# PIC32.net
KiCad netlist of a schematic drawn in EAGLE
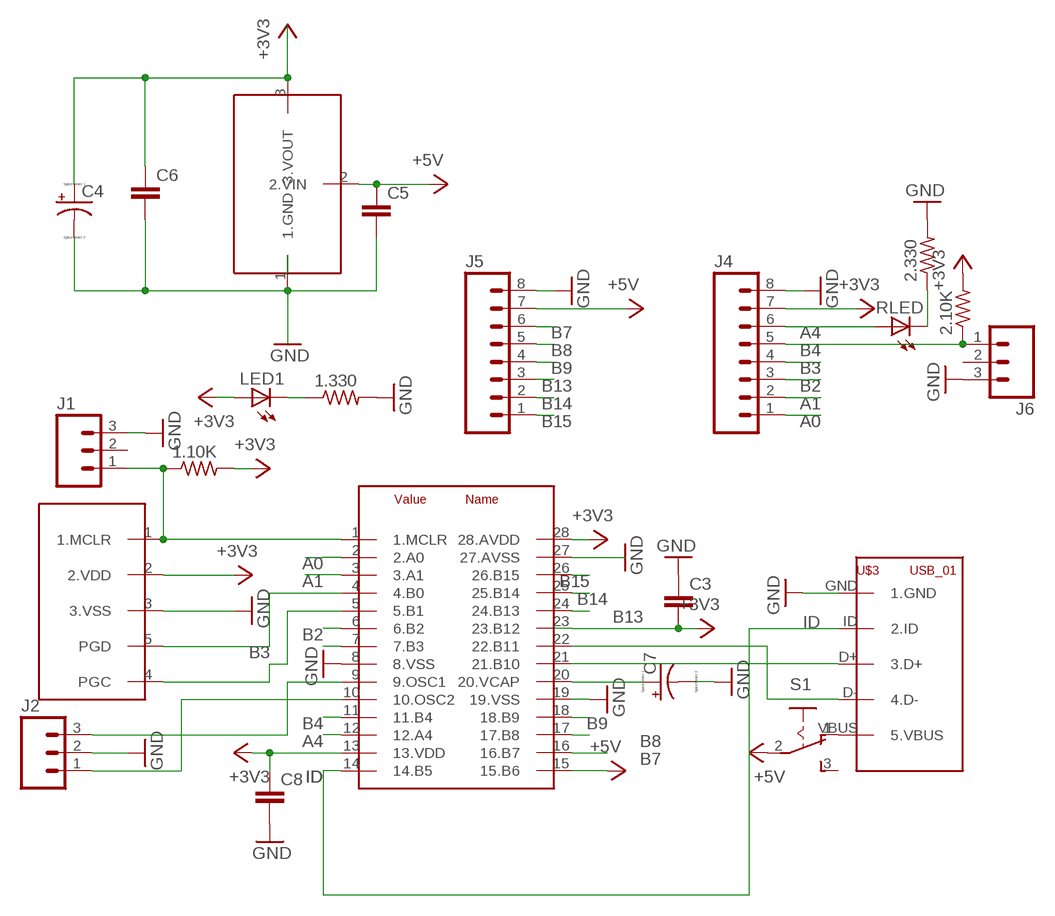
[diagram p0: schematic, sheet 1]

(export (version "E")
  (design (tool "Eeschema 10.0.6"))
  (components
    (comp (ref "1.10K")
      (value "R-US_0207/10")
      (footprint "eagle-import:0207_10")
      (libsource (lib "eagle-import") (part "R-US_0207/10"))
    )
    (comp (ref "1.330")
      (value "R-US_0207/10")
      (footprint "eagle-import:0207_10")
      (libsource (lib "eagle-import") (part "R-US_0207/10"))
    )
    (comp (ref "2.10K")
      (value "R-US_0207/10")
      (footprint "eagle-import:0207_10")
      (libsource (lib "eagle-import") (part "R-US_0207/10"))
    )
    (comp (ref "2.330")
      (value "R-US_0207/10")
      (footprint "eagle-import:0207_10")
      (libsource (lib "eagle-import") (part "R-US_0207/10"))
    )
    (comp (ref "C3")
      (value "C5/3")
      (footprint "eagle-import:C5B3")
      (libsource (lib "eagle-import") (part "C5/3"))
    )
    (comp (ref "C4")
      (value "CPOL-USB45181B")
      (footprint "eagle-import:B45181B")
      (libsource (lib "eagle-import") (part "CPOL-USB45181B"))
    )
    (comp (ref "C5")
      (value "C5/3")
      (footprint "eagle-import:C5B3")
      (libsource (lib "eagle-import") (part "C5/3"))
    )
    (comp (ref "C6")
      (value "C5/3")
      (footprint "eagle-import:C5B3")
      (libsource (lib "eagle-import") (part "C5/3"))
    )
    (comp (ref "C7")
      (value "CPOL-USB45181B")
      (footprint "eagle-import:B45181B")
      (libsource (lib "eagle-import") (part "CPOL-USB45181B"))
    )
    (comp (ref "C8")
      (value "C5/3")
      (footprint "eagle-import:C5B3")
      (libsource (lib "eagle-import") (part "C5/3"))
    )
    (comp (ref "J1")
      (value "M03PTH")
      (footprint "eagle-import:1X03")
      (libsource (lib "eagle-import") (part "M03PTH"))
    )
    (comp (ref "J2")
      (value "M03PTH")
      (footprint "eagle-import:1X03")
      (libsource (lib "eagle-import") (part "M03PTH"))
    )
    (comp (ref "J4")
      (value "M08")
      (footprint "eagle-import:1X08_ROUND")
      (libsource (lib "eagle-import") (part "M08"))
    )
    (comp (ref "J5")
      (value "M08")
      (footprint "eagle-import:1X08_ROUND")
      (libsource (lib "eagle-import") (part "M08"))
    )
    (comp (ref "J6")
      (value "M03PTH")
      (footprint "eagle-import:1X03")
      (libsource (lib "eagle-import") (part "M03PTH"))
    )
    (comp (ref "LED1")
      (value "LED3MM")
      (footprint "eagle-import:LED3MM")
      (libsource (lib "eagle-import") (part "LED3MM"))
    )
    (comp (ref "RLED")
      (value "LED3MM")
      (footprint "eagle-import:LED3MM")
      (libsource (lib "eagle-import") (part "LED3MM"))
    )
    (comp (ref "S1")
      (value "255SB")
      (footprint "eagle-import:255SB")
      (libsource (lib "eagle-import") (part "255SB"))
    )
    (comp (ref "U$1")
      (value "PIC28")
      (footprint "eagle-import:DIL28-3")
      (libsource (lib "eagle-import") (part "PIC28"))
    )
    (comp (ref "U$2")
      (value "MCP1702")
      (footprint "eagle-import:TO92")
      (libsource (lib "eagle-import") (part "MCP1702"))
    )
    (comp (ref "U$3")
      (value "USB_01")
      (footprint "eagle-import:USB-MB-H")
      (libsource (lib "eagle-import") (part "USB_01"))
    )
    (comp (ref "U$5")
      (value "SWITCH_M05")
      (footprint "eagle-import:1X05")
      (libsource (lib "eagle-import") (part "SWITCH_M05"))
    )
  )
  (nets
    (net (code "1") (name "+3V3") (class "Default")
      (node (ref "1.10K") (pin "2") (pinfunction "2_2") (pintype "passive"))
      (node (ref "2.10K") (pin "2") (pinfunction "2_2") (pintype "passive"))
      (node (ref "C3") (pin "2") (pinfunction "2_2") (pintype "passive"))
      (node (ref "C8") (pin "1") (pinfunction "1_1") (pintype "passive"))
      (node (ref "J4") (pin "7") (pinfunction "7_7") (pintype "passive"))
      (node (ref "LED1") (pin "A") (pinfunction "A_A") (pintype "passive"))
      (node (ref "U$1") (pin "13") (pinfunction "13.VDD_13") (pintype "bidirectional"))
      (node (ref "U$1") (pin "23") (pinfunction "23.B12_23") (pintype "bidirectional"))
      (node (ref "U$1") (pin "28") (pinfunction "28.AVDD_28") (pintype "bidirectional"))
      (node (ref "U$5") (pin "2") (pinfunction "2.VDD_2") (pintype "bidirectional"))
    )
    (net (code "2") (name "+5V") (class "Default")
      (node (ref "C5") (pin "1") (pinfunction "1_1") (pintype "passive"))
      (node (ref "J5") (pin "7") (pinfunction "7_7") (pintype "passive"))
      (node (ref "S1") (pin "2") (pinfunction "P_2") (pintype "passive"))
      (node (ref "U$1") (pin "15") (pinfunction "15.B6_15") (pintype "bidirectional"))
      (node (ref "U$2") (pin "2") (pinfunction "2.VIN_2") (pintype "bidirectional"))
    )
    (net (code "3") (name "/A0") (class "Default")
      (node (ref "J4") (pin "1") (pinfunction "1_1") (pintype "passive"))
      (node (ref "U$1") (pin "2") (pinfunction "2.A0_2") (pintype "bidirectional"))
    )
    (net (code "4") (name "/A1") (class "Default")
      (node (ref "J4") (pin "2") (pinfunction "2_2") (pintype "passive"))
      (node (ref "U$1") (pin "3") (pinfunction "3.A1_3") (pintype "bidirectional"))
    )
    (net (code "5") (name "/A4") (class "Default")
      (node (ref "J4") (pin "6") (pinfunction "6_6") (pintype "passive"))
      (node (ref "RLED") (pin "A") (pinfunction "A_A") (pintype "passive"))
      (node (ref "U$1") (pin "12") (pinfunction "12.A4_12") (pintype "bidirectional"))
    )
    (net (code "6") (name "/B2") (class "Default")
      (node (ref "J4") (pin "3") (pinfunction "3_3") (pintype "passive"))
      (node (ref "U$1") (pin "6") (pinfunction "6.B2_6") (pintype "bidirectional"))
    )
    (net (code "7") (name "/B3") (class "Default")
      (node (ref "J4") (pin "4") (pinfunction "4_4") (pintype "passive"))
      (node (ref "U$1") (pin "7") (pinfunction "7.B3_7") (pintype "bidirectional"))
    )
    (net (code "8") (name "/B4") (class "Default")
      (node (ref "2.10K") (pin "1") (pinfunction "1_1") (pintype "passive"))
      (node (ref "J4") (pin "5") (pinfunction "5_5") (pintype "passive"))
      (node (ref "J6") (pin "1") (pinfunction "1_1") (pintype "passive"))
      (node (ref "U$1") (pin "11") (pinfunction "11.B4_11") (pintype "bidirectional"))
    )
    (net (code "9") (name "/B7") (class "Default")
      (node (ref "J5") (pin "6") (pinfunction "6_6") (pintype "passive"))
      (node (ref "U$1") (pin "16") (pinfunction "16.B7_16") (pintype "bidirectional"))
    )
    (net (code "10") (name "/B8") (class "Default")
      (node (ref "J5") (pin "5") (pinfunction "5_5") (pintype "passive"))
      (node (ref "U$1") (pin "17") (pinfunction "17.B8_17") (pintype "bidirectional"))
    )
    (net (code "11") (name "/B9") (class "Default")
      (node (ref "J5") (pin "4") (pinfunction "4_4") (pintype "passive"))
      (node (ref "U$1") (pin "18") (pinfunction "18.B9_18") (pintype "bidirectional"))
    )
    (net (code "12") (name "/B13") (class "Default")
      (node (ref "J5") (pin "3") (pinfunction "3_3") (pintype "passive"))
      (node (ref "U$1") (pin "24") (pinfunction "24.B13_24") (pintype "bidirectional"))
    )
    (net (code "13") (name "/B14") (class "Default")
      (node (ref "J5") (pin "2") (pinfunction "2_2") (pintype "passive"))
      (node (ref "U$1") (pin "25") (pinfunction "25.B14_25") (pintype "bidirectional"))
    )
    (net (code "14") (name "/B15") (class "Default")
      (node (ref "J5") (pin "1") (pinfunction "1_1") (pintype "passive"))
      (node (ref "U$1") (pin "26") (pinfunction "26.B15_26") (pintype "bidirectional"))
    )
    (net (code "15") (name "/ID") (class "Default")
      (node (ref "U$1") (pin "14") (pinfunction "14.B5_14") (pintype "bidirectional"))
      (node (ref "U$3") (pin "ID") (pinfunction "2.ID_ID") (pintype "bidirectional"))
    )
    (net (code "16") (name "GND") (class "Default")
      (node (ref "1.330") (pin "2") (pinfunction "2_2") (pintype "passive"))
      (node (ref "2.330") (pin "2") (pinfunction "2_2") (pintype "passive"))
      (node (ref "C3") (pin "1") (pinfunction "1_1") (pintype "passive"))
      (node (ref "C7") (pin "-") (pinfunction "-_-") (pintype "passive"))
      (node (ref "C8") (pin "2") (pinfunction "2_2") (pintype "passive"))
      (node (ref "J1") (pin "3") (pinfunction "3_3") (pintype "passive"))
      (node (ref "J2") (pin "2") (pinfunction "2_2") (pintype "passive"))
      (node (ref "J4") (pin "8") (pinfunction "8_8") (pintype "passive"))
      (node (ref "J5") (pin "8") (pinfunction "8_8") (pintype "passive"))
      (node (ref "J6") (pin "3") (pinfunction "3_3") (pintype "passive"))
      (node (ref "U$1") (pin "19") (pinfunction "19.VSS_19") (pintype "bidirectional"))
      (node (ref "U$1") (pin "8") (pinfunction "8.VSS_8") (pintype "bidirectional"))
      (node (ref "U$3") (pin "GND") (pinfunction "1.GND_GND") (pintype "bidirectional"))
      (node (ref "U$5") (pin "3") (pinfunction "3.VSS_3") (pintype "bidirectional"))
    )
    (net (code "17") (name "Net-(LED1-C)") (class "Default")
      (node (ref "1.330") (pin "1") (pinfunction "1_1") (pintype "passive"))
      (node (ref "LED1") (pin "K") (pinfunction "C_K") (pintype "passive"))
    )
    (net (code "18") (name "Net-(RLED-C)") (class "Default")
      (node (ref "2.330") (pin "1") (pinfunction "1_1") (pintype "passive"))
      (node (ref "RLED") (pin "K") (pinfunction "C_K") (pintype "passive"))
    )
    (net (code "19") (name "Net-(S1-O)") (class "Default")
      (node (ref "S1") (pin "1") (pinfunction "O_1") (pintype "passive"))
      (node (ref "U$3") (pin "VBUS") (pinfunction "5.VBUS_VBUS") (pintype "bidirectional"))
    )
    (net (code "20") (name "Net-(U$1-1.MCLR)") (class "Default")
      (node (ref "1.10K") (pin "1") (pinfunction "1_1") (pintype "passive"))
      (node (ref "J1") (pin "1") (pinfunction "1_1") (pintype "passive"))
      (node (ref "U$1") (pin "1") (pinfunction "1.MCLR_1") (pintype "bidirectional"))
      (node (ref "U$5") (pin "1") (pinfunction "1.MCLR_1") (pintype "bidirectional"))
    )
    (net (code "21") (name "Net-(U$1-4.B0)") (class "Default")
      (node (ref "U$1") (pin "4") (pinfunction "4.B0_4") (pintype "bidirectional"))
      (node (ref "U$5") (pin "5") (pinfunction "PGD_5") (pintype "bidirectional"))
    )
    (net (code "22") (name "Net-(U$1-5.B1)") (class "Default")
      (node (ref "U$1") (pin "5") (pinfunction "5.B1_5") (pintype "bidirectional"))
      (node (ref "U$5") (pin "4") (pinfunction "PGC_4") (pintype "bidirectional"))
    )
    (net (code "23") (name "Net-(U$1-9.OSC1)") (class "Default")
      (node (ref "J2") (pin "3") (pinfunction "3_3") (pintype "passive"))
      (node (ref "U$1") (pin "9") (pinfunction "9.OSC1_9") (pintype "bidirectional"))
    )
    (net (code "24") (name "Net-(U$1-10.OSC2)") (class "Default")
      (node (ref "J2") (pin "1") (pinfunction "1_1") (pintype "passive"))
      (node (ref "U$1") (pin "10") (pinfunction "10.OSC2_10") (pintype "bidirectional"))
    )
    (net (code "25") (name "Net-(U$1-20.VCAP)") (class "Default")
      (node (ref "C7") (pin "+") (pinfunction "+_+") (pintype "passive"))
      (node (ref "U$1") (pin "20") (pinfunction "20.VCAP_20") (pintype "bidirectional"))
    )
    (net (code "26") (name "Net-(U$1-21.B10)") (class "Default")
      (node (ref "U$1") (pin "21") (pinfunction "21.B10_21") (pintype "bidirectional"))
      (node (ref "U$3") (pin "D+") (pinfunction "3.D+_D+") (pintype "bidirectional"))
    )
    (net (code "27") (name "Net-(U$1-22.B11)") (class "Default")
      (node (ref "U$1") (pin "22") (pinfunction "22.B11_22") (pintype "bidirectional"))
      (node (ref "U$3") (pin "D-") (pinfunction "4.D-_D-") (pintype "bidirectional"))
    )
    (net (code "28") (name "Net-(U$2-1.GND)") (class "Default")
      (node (ref "C4") (pin "-") (pinfunction "-_-") (pintype "passive"))
      (node (ref "C5") (pin "2") (pinfunction "2_2") (pintype "passive"))
      (node (ref "C6") (pin "2") (pinfunction "2_2") (pintype "passive"))
      (node (ref "U$2") (pin "1") (pinfunction "1.GND_1") (pintype "bidirectional"))
    )
    (net (code "29") (name "Net-(U$2-3.VOUT)") (class "Default")
      (node (ref "C4") (pin "+") (pinfunction "+_+") (pintype "passive"))
      (node (ref "C6") (pin "1") (pinfunction "1_1") (pintype "passive"))
      (node (ref "U$2") (pin "3") (pinfunction "3.VOUT_3") (pintype "bidirectional"))
    )
    (net (code "30") (name "unconnected-(J1-Pad2)") (class "Default")
      (node (ref "J1") (pin "2") (pinfunction "2_2") (pintype "passive"))
    )
    (net (code "31") (name "unconnected-(J6-Pad2)") (class "Default")
      (node (ref "J6") (pin "2") (pinfunction "2_2") (pintype "passive"))
    )
    (net (code "32") (name "unconnected-(S1-S-Pad3)") (class "Default")
      (node (ref "S1") (pin "3") (pinfunction "S_3") (pintype "passive"))
    )
    (net (code "33") (name "unconnected-(U$1-27.AVSS-Pad27)") (class "Default")
      (node (ref "U$1") (pin "27") (pinfunction "27.AVSS_27") (pintype "bidirectional"))
    )
  )
)
